# MCU098_01_MSPM0G3507_Target_Device.net
KiCad netlist of a schematic drawn in Altium Designer
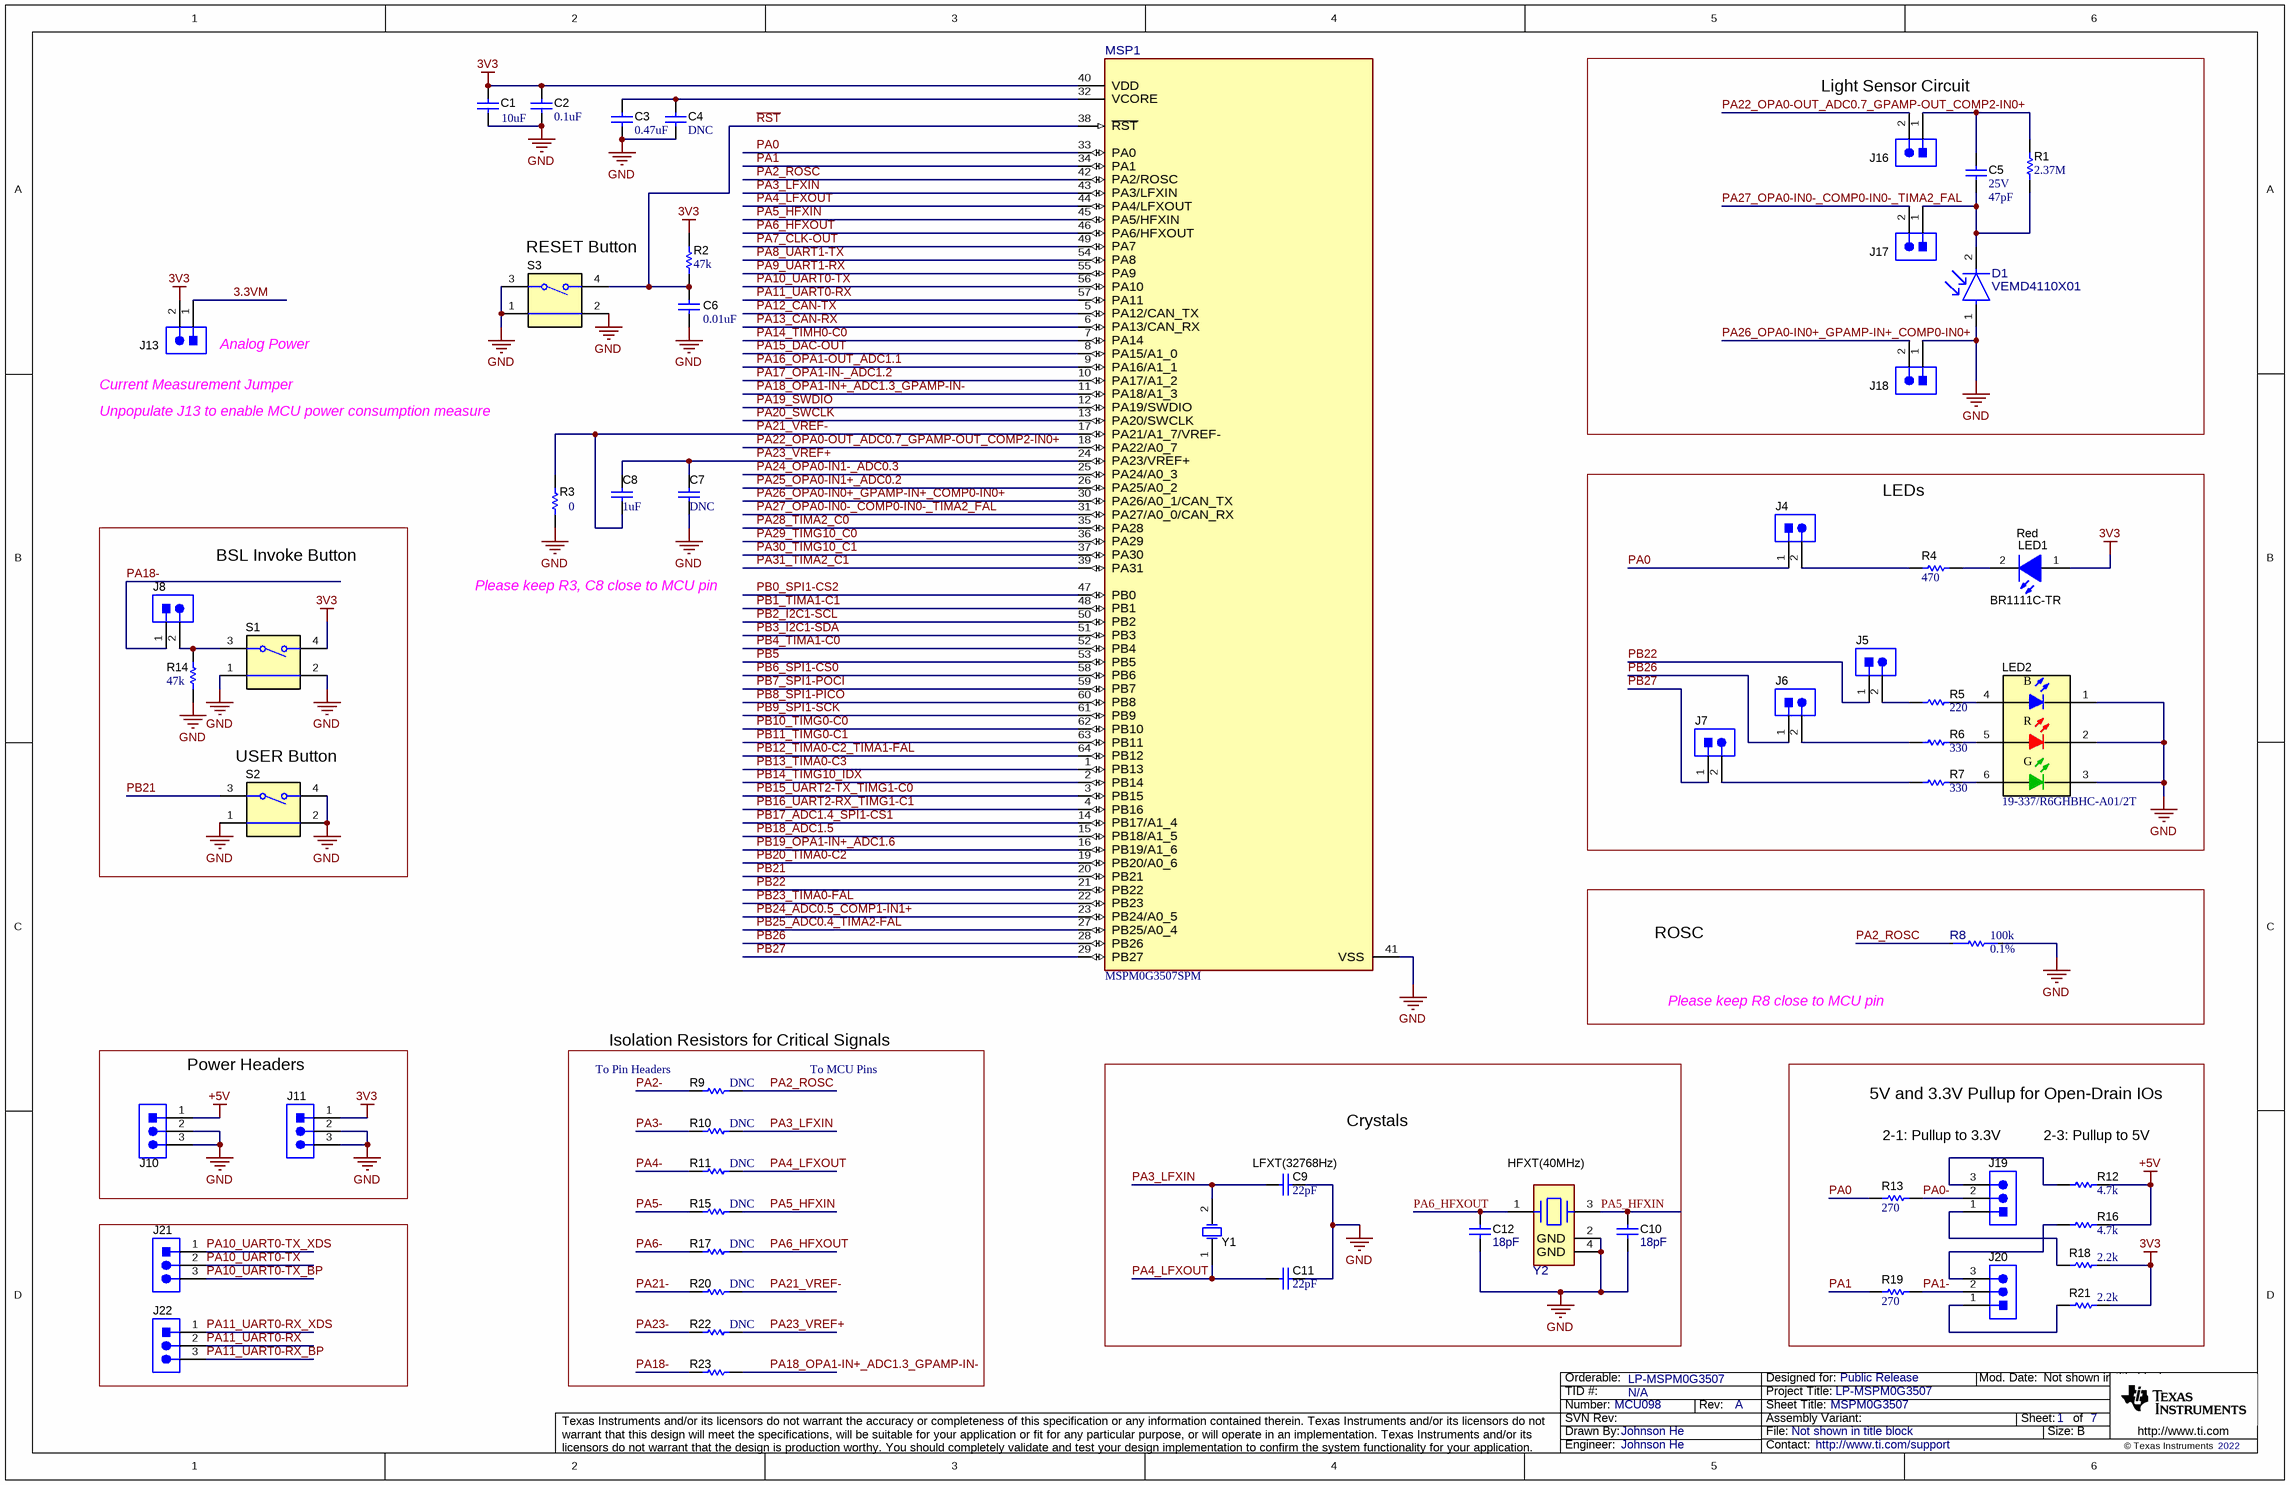
[diagram p0: MCU098_01_MSPM0G3507_Target_Device.SchDoc]

(export (version "E")
  (design (tool "Eeschema 10.0.6"))
  (components
    (comp (ref "C1")
      (value "GRM188R60J106ME84")
      (footprint "0603")
      (description "CAP, CERM, 10 uF, 6.3 V, +/- 20%, X5R, 0603")
      (fields
        (field (name "MANUFACTURER") "MuRata")
        (field (name "VALUEDISPLAYED") "10uF")
        (field (name "PUBLISHER") "Texas Instruments")
      )
      (libsource (lib "Altium Vault - TI") (part "Capacitor"))
    )
    (comp (ref "C2")
      (value "GRM155R61H104ME14D")
      (footprint "0402")
      (description "CAP, CERM, 0.1 uF, 50 V, +/- 20%, X5R, 0402")
      (fields
        (field (name "MANUFACTURER") "MuRata")
        (field (name "VALUEDISPLAYED") "0.1uF")
        (field (name "PUBLISHER") "Texas Instruments")
      )
      (libsource (lib "Altium Vault - TI") (part "Capacitor"))
    )
    (comp (ref "C3")
      (value "GRM155R60J474KE19D")
      (footprint "0402")
      (description "CAP, CERM, 0.47 uF, 6.3 V, +/- 10%, X5R, 0402")
      (fields
        (field (name "MANUFACTURER") "MuRata")
        (field (name "VALUEDISPLAYED") "0.47uF")
        (field (name "PUBLISHER") "Texas Instruments")
      )
      (libsource (lib "Altium Vault - TI") (part "Capacitor"))
    )
    (comp (ref "C4")
      (value "GRM155R61H104ME14D")
      (footprint "0402")
      (description "CAP, CERM, 0.1 uF, 50 V, +/- 20%, X5R, 0402")
      (fields
        (field (name "MANUFACTURER") "MuRata")
        (field (name "VALUEDISPLAYED") "DNC")
        (field (name "PUBLISHER") "Texas Instruments")
      )
      (libsource (lib "Altium Vault - TI") (part "Capacitor"))
    )
    (comp (ref "C5")
      (value "GRM1555C1E470JA01D")
      (footprint "0402")
      (description "CAP, CERM, 47 pF, 25 V, +/- 5%, C0G/NP0, 0402")
      (fields
        (field (name "MANUFACTURER") "MuRata")
        (field (name "VDC_V") "25V")
        (field (name "VALUEDISPLAYED") "47pF")
        (field (name "PUBLISHER") "Texas Instruments")
      )
      (libsource (lib "Altium Vault - TI") (part "Capacitor"))
    )
    (comp (ref "C6")
      (value "GRM155R61C103KA01D")
      (footprint "0402")
      (description "CAP, CERM, 0.01 uF, 16 V, +/- 10%, X5R, 0402")
      (fields
        (field (name "MANUFACTURER") "MuRata")
        (field (name "VALUEDISPLAYED") "0.01uF")
        (field (name "PUBLISHER") "Texas Instruments")
      )
      (libsource (lib "Altium Vault - TI") (part "Capacitor"))
    )
    (comp (ref "C7")
      (value "C1608X5R1E105K080AC")
      (footprint "0603")
      (description "CAP, CERM, 1 uF, 25 V, +/- 10%, X5R, 0603")
      (fields
        (field (name "MANUFACTURER") "TDK")
        (field (name "VALUEDISPLAYED") "DNC")
        (field (name "PUBLISHER") "Texas Instruments")
      )
      (libsource (lib "Altium Vault - TI") (part "Capacitor"))
    )
    (comp (ref "C8")
      (value "1uF")
      (footprint "0603")
      (description "CAP, CERM, 1 uF, 25 V, +/- 10%, X5R, 0603")
      (fields
        (field (name "MANUFACTURER") "TDK")
        (field (name "PARTNUMBER") "C1608X5R1E105K080AC")
        (field (name "PUBLISHER") "Texas Instruments")
      )
      (libsource (lib "Altium Vault - TI") (part "Capacitor"))
    )
    (comp (ref "C9")
      (value "GRM1555C1H220JA01D")
      (footprint "0402")
      (description "CAP, CERM, 22 pF, 50 V, +/- 5%, C0G/NP0, 0402")
      (fields
        (field (name "MANUFACTURER") "MuRata")
        (field (name "VALUEDISPLAYED") "22pF")
        (field (name "PUBLISHER") "Texas Instruments")
      )
      (libsource (lib "Altium Vault - TI") (part "Capacitor"))
    )
    (comp (ref "C10")
      (value "GRM1555C1H220JA01D")
      (footprint "0402")
      (description "CAP, CERM, 22 pF, 50 V, +/- 5%, C0G/NP0, 0402")
      (fields
        (field (name "MANUFACTURER") "MuRata")
        (field (name "VALUEDISPLAYED") "18pF")
        (field (name "PUBLISHER") "Texas Instruments")
      )
      (libsource (lib "Altium Vault - TI") (part "Capacitor"))
    )
    (comp (ref "C11")
      (value "GRM1555C1H220JA01D")
      (footprint "0402")
      (description "CAP, CERM, 22 pF, 50 V, +/- 5%, C0G/NP0, 0402")
      (fields
        (field (name "MANUFACTURER") "MuRata")
        (field (name "VALUEDISPLAYED") "22pF")
        (field (name "PUBLISHER") "Texas Instruments")
      )
      (libsource (lib "Altium Vault - TI") (part "Capacitor"))
    )
    (comp (ref "C12")
      (value "GRM1555C1H220JA01D")
      (footprint "0402")
      (description "CAP, CERM, 22 pF, 50 V, +/- 5%, C0G/NP0, 0402")
      (fields
        (field (name "MANUFACTURER") "MuRata")
        (field (name "VALUEDISPLAYED") "18pF")
        (field (name "PUBLISHER") "Texas Instruments")
      )
      (libsource (lib "Altium Vault - TI") (part "Capacitor"))
    )
    (comp (ref "D1")
      (value "VEMD4110X01")
      (footprint "FP-VEMD4110X01_0805-MFG")
      (description "Photodiode PIN Chip 910nm Automotive 2-Pin Case 0805(2012Metric) T/R")
      (fields
        (field (name "MANUFACTURER") "Vishay")
        (field (name "DIGIKEY PART NUMBER") "751-VEMD4110X01CT-ND")
      )
      (libsource (lib "Altium Vault - TI") (part "SYM-VEMD4110X01"))
    )
    (comp (ref "J4")
      (value "90120-0122")
      (footprint "CONN_90120-0122")
      (description "Header, 100mil, 2x1, Tin, TH")
      (fields (field (name "MANUFACTURER") "Molex") (field (name "PUBLISHER") "Texas Instruments"))
      (libsource (lib "Altium Vault - TI") (part "Header_2x1"))
    )
    (comp (ref "J5")
      (value "90120-0122")
      (footprint "CONN_90120-0122")
      (description "Header, 100mil, 2x1, Tin, TH")
      (fields (field (name "MANUFACTURER") "Molex") (field (name "PUBLISHER") "Texas Instruments"))
      (libsource (lib "Altium Vault - TI") (part "Header_2x1"))
    )
    (comp (ref "J6")
      (value "90120-0122")
      (footprint "CONN_90120-0122")
      (description "Header, 100mil, 2x1, Tin, TH")
      (fields (field (name "MANUFACTURER") "Molex") (field (name "PUBLISHER") "Texas Instruments"))
      (libsource (lib "Altium Vault - TI") (part "Header_2x1"))
    )
    (comp (ref "J7")
      (value "90120-0122")
      (footprint "CONN_90120-0122")
      (description "Header, 100mil, 2x1, Tin, TH")
      (fields (field (name "MANUFACTURER") "Molex") (field (name "PUBLISHER") "Texas Instruments"))
      (libsource (lib "Altium Vault - TI") (part "Header_2x1"))
    )
    (comp (ref "J8")
      (value "90120-0122")
      (footprint "CONN_90120-0122")
      (description "Header, 100mil, 2x1, Tin, TH")
      (fields (field (name "MANUFACTURER") "Molex") (field (name "PUBLISHER") "Texas Instruments"))
      (libsource (lib "Altium Vault - TI") (part "Header_2x1"))
    )
    (comp (ref "J10")
      (value "PEC03SAAN")
      (footprint "PEC03SAAN_Launchpad_5V0")
      (description "Header, 100mil, 3x1, Tin, TH")
      (fields
        (field (name "MANUFACTURER") "Sullins Connector Solutions")
        (field (name "PUBLISHER") "Texas Instruments")
      )
      (libsource (lib "Altium Vault - TI") (part "Header_3x1_Launchpad"))
    )
    (comp (ref "J11")
      (value "PEC03SAAN")
      (footprint "PEC03SAAN_Launchpad_3V3")
      (description "Header, 100mil, 3x1, Tin, TH")
      (fields
        (field (name "MANUFACTURER") "Sullins Connector Solutions")
        (field (name "PUBLISHER") "Texas Instruments")
      )
      (libsource (lib "Altium Vault - TI") (part "Header_3x1_Launchpad"))
    )
    (comp (ref "J13")
      (value "90120-0122")
      (footprint "CONN_90120-0122")
      (description "Header, 100mil, 2x1, Tin, TH")
      (fields (field (name "MANUFACTURER") "Molex") (field (name "PUBLISHER") "Texas Instruments"))
      (libsource (lib "") (part "Header_2x1_1"))
    )
    (comp (ref "J16")
      (value "90120-0122")
      (footprint "CONN_90120-0122")
      (description "Header, 100mil, 2x1, Tin, TH")
      (fields (field (name "MANUFACTURER") "Molex") (field (name "PUBLISHER") "Texas Instruments"))
      (libsource (lib "") (part "Header_2x1_1"))
    )
    (comp (ref "J17")
      (value "90120-0122")
      (footprint "CONN_90120-0122")
      (description "Header, 100mil, 2x1, Tin, TH")
      (fields (field (name "MANUFACTURER") "Molex") (field (name "PUBLISHER") "Texas Instruments"))
      (libsource (lib "") (part "Header_2x1_1"))
    )
    (comp (ref "J18")
      (value "90120-0122")
      (footprint "CONN_90120-0122")
      (description "Header, 100mil, 2x1, Tin, TH")
      (fields (field (name "MANUFACTURER") "Molex") (field (name "PUBLISHER") "Texas Instruments"))
      (libsource (lib "") (part "Header_2x1_1"))
    )
    (comp (ref "J19")
      (value "PEC03SAAN")
      (footprint "CONN_PEC03SAAN")
      (description "Header, 100mil, 3x1, Tin, TH")
      (fields
        (field (name "MANUFACTURER") "Sullins Connector Solutions")
        (field (name "PUBLISHER") "Texas Instruments")
      )
      (libsource (lib "") (part "Header_3x1_Launchpad_1"))
    )
    (comp (ref "J20")
      (value "PEC03SAAN")
      (footprint "CONN_PEC03SAAN")
      (description "Header, 100mil, 3x1, Tin, TH")
      (fields
        (field (name "MANUFACTURER") "Sullins Connector Solutions")
        (field (name "PUBLISHER") "Texas Instruments")
      )
      (libsource (lib "") (part "Header_3x1_Launchpad_1"))
    )
    (comp (ref "J21")
      (value "PEC03SAAN")
      (footprint "CONN_PEC03SAAN")
      (description "Header, 100mil, 3x1, Tin, TH")
      (fields
        (field (name "MANUFACTURER") "Sullins Connector Solutions")
        (field (name "PUBLISHER") "Texas Instruments")
      )
      (libsource (lib "Altium Vault - TI") (part "Header_3x1_Launchpad"))
    )
    (comp (ref "J22")
      (value "PEC03SAAN")
      (footprint "CONN_PEC03SAAN")
      (description "Header, 100mil, 3x1, Tin, TH")
      (fields
        (field (name "MANUFACTURER") "Sullins Connector Solutions")
        (field (name "PUBLISHER") "Texas Instruments")
      )
      (libsource (lib "Altium Vault - TI") (part "Header_3x1_Launchpad"))
    )
    (comp (ref "LED1")
      (value "BR1111C-TR")
      (footprint "1111C_Red")
      (description "LED, Red, SMD")
      (fields (field (name "ALTIUM_VALUE") "Red") (field (name "MANUFACTURER") "Stanley Electric Co., LTD"))
      (libsource (lib "Altium Vault - TI") (part "LED"))
    )
    (comp (ref "LED2")
      (value "19-337/R6GHBHC-A01/2T")
      (footprint "19-337_RGB")
      (description "LED, RGB, SMD")
      (fields (field (name "MANUFACTURER") "Everlight") (field (name "PUBLISHER") "Texas Instruments"))
      (libsource (lib "Altium Vault - TI") (part "LED_RGB_A456K123"))
    )
    (comp (ref "MSP1")
      (value "MSPM0G3507SPM")
      (footprint "PM0064A-MFG")
      (description "Mixed-Signal Microcontrollers With CAN-FD Interface LQFP64")
      (fields (field (name "PARTNUMBER") "MSPM0G3507SPM") (field (name "MANUFACTURER") "Texas Instruments"))
      (libsource (lib "Altium Vault - TI") (part "SYM-MSPM0G3507SPM"))
    )
    (comp (ref "R1")
      (value "CRCW06032M37FKEA")
      (footprint "0603")
      (description "RES, 2.37 M, 1%, 0.1 W, 0603")
      (fields
        (field (name "MANUFACTURER") "Vishay-Dale")
        (field (name "VALUEDISPLAYED") "2.37M")
        (field (name "PUBLISHER") "Texas Instruments")
      )
      (libsource (lib "Altium Vault - TI") (part "Resistor"))
    )
    (comp (ref "R2")
      (value "CRCW040247K0JNED")
      (footprint "0402")
      (description "RES, 47 k, 5%, 0.063 W, 0402")
      (fields
        (field (name "MANUFACTURER") "Vishay-Dale")
        (field (name "VALUEDISPLAYED") "47k")
        (field (name "PUBLISHER") "Texas Instruments")
      )
      (libsource (lib "Altium Vault - TI") (part "Resistor"))
    )
    (comp (ref "R3")
      (value "0")
      (footprint "0603")
      (description "RES, 0, 5%, 0.1 W, 0603")
      (fields (field (name "MANUFACTURER") "Yageo") (field (name "PARTNUMBER") "RC0603JR-070RL"))
      (libsource (lib "Altium Vault - TI") (part "Resistor"))
    )
    (comp (ref "R4")
      (value "CRCW0402470RJNED")
      (footprint "0402")
      (description "RES, 470, 5%, 0.063 W, 0402")
      (fields
        (field (name "MANUFACTURER") "Vishay-Dale")
        (field (name "VALUEDISPLAYED") "470")
        (field (name "PUBLISHER") "Texas Instruments")
      )
      (libsource (lib "Altium Vault - TI") (part "Resistor"))
    )
    (comp (ref "R5")
      (value "CRCW0402220RJNED")
      (footprint "0402")
      (description "RES, 220, 5%, 0.063 W, 0402")
      (fields
        (field (name "MANUFACTURER") "Vishay-Dale")
        (field (name "VALUEDISPLAYED") "220")
        (field (name "PUBLISHER") "Texas Instruments")
      )
      (libsource (lib "Altium Vault - TI") (part "Resistor"))
    )
    (comp (ref "R6")
      (value "CRCW0402330RJNED")
      (footprint "0402")
      (description "RES, 330, 5%, 0.063 W, 0402")
      (fields
        (field (name "MANUFACTURER") "Vishay-Dale")
        (field (name "VALUEDISPLAYED") "330")
        (field (name "PUBLISHER") "Texas Instruments")
      )
      (libsource (lib "Altium Vault - TI") (part "Resistor"))
    )
    (comp (ref "R7")
      (value "CRCW0402330RJNED")
      (footprint "0402")
      (description "RES, 330, 5%, 0.063 W, 0402")
      (fields
        (field (name "MANUFACTURER") "Vishay-Dale")
        (field (name "VALUEDISPLAYED") "330")
        (field (name "PUBLISHER") "Texas Instruments")
      )
      (libsource (lib "Altium Vault - TI") (part "Resistor"))
    )
    (comp (ref "R8")
      (value "ERA-2AEB104X")
      (footprint "FP-ERA-2AEB104X_0402-MFG")
      (description "Res Thin Film 0402 100K Ohm 0.1% 1/16W ±25ppm/°C Molded SMD SMD Punched Carrier T/R")
      (fields
        (field (name "DIGIKEY PART NUMBER") "P100KDCCT-ND")
        (field (name "MANUFACTURER") "Panasonic")
        (field (name "TOLERANCE_%") "0.1%")
        (field (name "RES_OHM") "100k")
      )
      (libsource (lib "Altium Vault - TI") (part "SYM-ERA-2AEB104X"))
    )
    (comp (ref "R9")
      (value "RC0402JR-070RL")
      (footprint "0402")
      (description "RES, 0, 5%, 0.063 W, 0402")
      (fields
        (field (name "MANUFACTURER") "Yageo America")
        (field (name "VALUEDISPLAYED") "DNC")
        (field (name "PUBLISHER") "Texas Instruments")
      )
      (libsource (lib "Altium Vault - TI") (part "Resistor"))
    )
    (comp (ref "R10")
      (value "RC0402JR-070RL")
      (footprint "0402")
      (description "RES, 0, 5%, 0.063 W, 0402")
      (fields
        (field (name "MANUFACTURER") "Yageo America")
        (field (name "VALUEDISPLAYED") "DNC")
        (field (name "PUBLISHER") "Texas Instruments")
      )
      (libsource (lib "Altium Vault - TI") (part "Resistor"))
    )
    (comp (ref "R11")
      (value "RC0402JR-070RL")
      (footprint "0402")
      (description "RES, 0, 5%, 0.063 W, 0402")
      (fields
        (field (name "MANUFACTURER") "Yageo America")
        (field (name "VALUEDISPLAYED") "DNC")
        (field (name "PUBLISHER") "Texas Instruments")
      )
      (libsource (lib "Altium Vault - TI") (part "Resistor"))
    )
    (comp (ref "R12")
      (value "RC0603JR-074K7L")
      (footprint "0603")
      (description "RES, 4.7 k, 5%, 0.1 W, 0603")
      (fields (field (name "MANUFACTURER") "Yageo") (field (name "VALUEDISPLAYED") "4.7k"))
      (libsource (lib "Altium Vault - TI") (part "Resistor"))
    )
    (comp (ref "R13")
      (value "CRCW0402270RJNED")
      (footprint "0402")
      (description "RES, 270, 5%, 0.063 W, 0402")
      (fields
        (field (name "MANUFACTURER") "Vishay-Dale")
        (field (name "VALUEDISPLAYED") "270")
        (field (name "PUBLISHER") "Texas Instruments")
      )
      (libsource (lib "Altium Vault - TI") (part "Resistor"))
    )
    (comp (ref "R14")
      (value "CRCW040247K0JNED")
      (footprint "0402")
      (description "RES, 47 k, 5%, 0.063 W, 0402")
      (fields
        (field (name "MANUFACTURER") "Vishay-Dale")
        (field (name "VALUEDISPLAYED") "47k")
        (field (name "PUBLISHER") "Texas Instruments")
      )
      (libsource (lib "Altium Vault - TI") (part "Resistor"))
    )
    (comp (ref "R15")
      (value "RC0402JR-070RL")
      (footprint "0402")
      (description "RES, 0, 5%, 0.063 W, 0402")
      (fields
        (field (name "MANUFACTURER") "Yageo America")
        (field (name "VALUEDISPLAYED") "DNC")
        (field (name "PUBLISHER") "Texas Instruments")
      )
      (libsource (lib "Altium Vault - TI") (part "Resistor"))
    )
    (comp (ref "R16")
      (value "RC0603JR-074K7L")
      (footprint "0603")
      (description "RES, 4.7 k, 5%, 0.1 W, 0603")
      (fields (field (name "MANUFACTURER") "Yageo") (field (name "VALUEDISPLAYED") "4.7k"))
      (libsource (lib "Altium Vault - TI") (part "Resistor"))
    )
    (comp (ref "R17")
      (value "RC0402JR-070RL")
      (footprint "0402")
      (description "RES, 0, 5%, 0.063 W, 0402")
      (fields
        (field (name "MANUFACTURER") "Yageo America")
        (field (name "VALUEDISPLAYED") "DNC")
        (field (name "PUBLISHER") "Texas Instruments")
      )
      (libsource (lib "Altium Vault - TI") (part "Resistor"))
    )
    (comp (ref "R18")
      (value "RC0603JR-0710KL")
      (footprint "0603")
      (description "RES, 2.2 k, 5%, 0.1 W, 0603")
      (fields
        (field (name "PARTNUMBER") "RC0603JR-072K2L")
        (field (name "MANUFACTURER") "Yageo")
        (field (name "VALUEDISPLAYED") "2.2k")
      )
      (libsource (lib "Altium Vault - TI") (part "Resistor"))
    )
    (comp (ref "R19")
      (value "CRCW0402270RJNED")
      (footprint "0402")
      (description "RES, 270, 5%, 0.063 W, 0402")
      (fields
        (field (name "MANUFACTURER") "Vishay-Dale")
        (field (name "VALUEDISPLAYED") "270")
        (field (name "PUBLISHER") "Texas Instruments")
      )
      (libsource (lib "Altium Vault - TI") (part "Resistor"))
    )
    (comp (ref "R20")
      (value "RC0402JR-070RL")
      (footprint "0402")
      (description "RES, 0, 5%, 0.063 W, 0402")
      (fields
        (field (name "MANUFACTURER") "Yageo America")
        (field (name "VALUEDISPLAYED") "DNC")
        (field (name "PUBLISHER") "Texas Instruments")
      )
      (libsource (lib "Altium Vault - TI") (part "Resistor"))
    )
    (comp (ref "R21")
      (value "RC0603JR-0710KL")
      (footprint "0603")
      (description "RES, 2.2 k, 5%, 0.1 W, 0603")
      (fields
        (field (name "PARTNUMBER") "RC0603JR-072K2L")
        (field (name "MANUFACTURER") "Yageo")
        (field (name "VALUEDISPLAYED") "2.2k")
      )
      (libsource (lib "Altium Vault - TI") (part "Resistor"))
    )
    (comp (ref "R22")
      (value "RC0402JR-070RL")
      (footprint "0402")
      (description "RES, 0, 5%, 0.063 W, 0402")
      (fields
        (field (name "MANUFACTURER") "Yageo America")
        (field (name "VALUEDISPLAYED") "DNC")
        (field (name "PUBLISHER") "Texas Instruments")
      )
      (libsource (lib "Altium Vault - TI") (part "Resistor"))
    )
    (comp (ref "R23")
      (value "RC0402JR-070RL")
      (footprint "0402")
      (description "RES, 0, 5%, 0.063 W, 0402")
      (fields (field (name "MANUFACTURER") "Yageo America") (field (name "PUBLISHER") "Texas Instruments"))
      (libsource (lib "Altium Vault - TI") (part "Resistor"))
    )
    (comp (ref "S1")
      (value "1188E-1K2-V-TR")
      (footprint "SW_1188E")
      (description "Switch, SPST, 0.05 A, 12 VDC, SMD")
      (fields (field (name "MANUFACTURER") "Diptronics") (field (name "PUBLISHER") "Texas Instruments"))
      (libsource (lib "Altium Vault - TI") (part "SW_1188E"))
    )
    (comp (ref "S2")
      (value "1188E-1K2-V-TR")
      (footprint "SW_1188E")
      (description "Switch, SPST, 0.05 A, 12 VDC, SMD")
      (fields (field (name "MANUFACTURER") "Diptronics") (field (name "PUBLISHER") "Texas Instruments"))
      (libsource (lib "Altium Vault - TI") (part "SW_1188E"))
    )
    (comp (ref "S3")
      (value "1188E-1K2-V-TR")
      (footprint "SW_1188E")
      (description "Switch, SPST, 0.05 A, 12 VDC, SMD")
      (fields (field (name "MANUFACTURER") "Diptronics") (field (name "PUBLISHER") "Texas Instruments"))
      (libsource (lib "Altium Vault - TI") (part "SW_1188E"))
    )
    (comp (ref "Y1")
      (value "X1A0001410014")
      (footprint "Epson_FC-135")
      (description "Crystal, 32.768 KHz, 12.5 pF, SMD")
      (fields (field (name "MANUFACTURER") "Epson") (field (name "PUBLISHER") "Texas Instruments"))
      (libsource (lib "Altium Vault - TI") (part "Xtal"))
    )
    (comp (ref "Y2")
      (value "X1E0000210179")
      (footprint "FP-X1E0000210179_TSX-3225-MFG")
      (description "Crystal 40MHz ±10ppm (Tol) ±20ppm (Stability) 12pF FUND 40Ohm 4-Pin Mini-CSMD T/R")
      (fields (field (name "MANUFACTURER") "Seiko Epson"))
      (libsource (lib "Altium Vault - TI") (part "SYM-X1E0000210179"))
    )
  )
  (nets
    (net (code "1") (name "+5V") (class "Default")
      (node (ref "J10") (pin "1") (pinfunction "1_1") (pintype "passive"))
      (node (ref "R12") (pin "2") (pinfunction "2_2") (pintype "passive"))
      (node (ref "R16") (pin "2") (pinfunction "2_2") (pintype "passive"))
    )
    (net (code "2") (name "/3.3VM") (class "Default")
      (node (ref "J13") (pin "1") (pinfunction "1_1") (pintype "passive"))
    )
    (net (code "3") (name "/PA0") (class "Default")
      (node (ref "J4") (pin "1") (pinfunction "1_1") (pintype "passive"))
      (node (ref "MSP1") (pin "33") (pinfunction "PA0_33") (pintype "bidirectional"))
      (node (ref "R13") (pin "1") (pinfunction "1_1") (pintype "passive"))
    )
    (net (code "4") (name "/PA0-") (class "Default")
      (node (ref "J19") (pin "2") (pinfunction "2_2") (pintype "passive"))
      (node (ref "R13") (pin "2") (pinfunction "2_2") (pintype "passive"))
    )
    (net (code "5") (name "/PA1") (class "Default")
      (node (ref "MSP1") (pin "34") (pinfunction "PA1_34") (pintype "bidirectional"))
      (node (ref "R19") (pin "1") (pinfunction "1_1") (pintype "passive"))
    )
    (net (code "6") (name "/PA1-") (class "Default")
      (node (ref "J20") (pin "2") (pinfunction "2_2") (pintype "passive"))
      (node (ref "R19") (pin "2") (pinfunction "2_2") (pintype "passive"))
    )
    (net (code "7") (name "/PA2-") (class "Default")
      (node (ref "R9") (pin "1") (pinfunction "1_1") (pintype "passive"))
    )
    (net (code "8") (name "/PA2_ROSC") (class "Default")
      (node (ref "MSP1") (pin "42") (pinfunction "PA2/ROSC_42") (pintype "bidirectional"))
      (node (ref "R8") (pin "1") (pinfunction "1_1") (pintype "passive"))
      (node (ref "R9") (pin "2") (pinfunction "2_2") (pintype "passive"))
    )
    (net (code "9") (name "/PA3-") (class "Default")
      (node (ref "R10") (pin "1") (pinfunction "1_1") (pintype "passive"))
    )
    (net (code "10") (name "/PA3_LFXIN") (class "Default")
      (node (ref "C9") (pin "2") (pinfunction "2_2") (pintype "passive"))
      (node (ref "MSP1") (pin "43") (pinfunction "PA3/LFXIN_43") (pintype "bidirectional"))
      (node (ref "R10") (pin "2") (pinfunction "2_2") (pintype "passive"))
      (node (ref "Y1") (pin "2") (pinfunction "OSC2_2") (pintype "passive"))
    )
    (net (code "11") (name "/PA4-") (class "Default")
      (node (ref "R11") (pin "1") (pinfunction "1_1") (pintype "passive"))
    )
    (net (code "12") (name "/PA4_LFXOUT") (class "Default")
      (node (ref "C11") (pin "2") (pinfunction "2_2") (pintype "passive"))
      (node (ref "MSP1") (pin "44") (pinfunction "PA4/LFXOUT_44") (pintype "bidirectional"))
      (node (ref "R11") (pin "2") (pinfunction "2_2") (pintype "passive"))
      (node (ref "Y1") (pin "1") (pinfunction "OSC1_1") (pintype "passive"))
    )
    (net (code "13") (name "/PA5-") (class "Default")
      (node (ref "R15") (pin "1") (pinfunction "1_1") (pintype "passive"))
    )
    (net (code "14") (name "/PA5_HFXIN") (class "Default")
      (node (ref "C10") (pin "2") (pinfunction "2_2") (pintype "passive"))
      (node (ref "MSP1") (pin "45") (pinfunction "PA5/HFXIN_45") (pintype "bidirectional"))
      (node (ref "R15") (pin "2") (pinfunction "2_2") (pintype "passive"))
      (node (ref "Y2") (pin "3") (pinfunction "3_3") (pintype "passive"))
    )
    (net (code "15") (name "/PA6-") (class "Default")
      (node (ref "R17") (pin "1") (pinfunction "1_1") (pintype "passive"))
    )
    (net (code "16") (name "/PA6_HFXOUT") (class "Default")
      (node (ref "C12") (pin "2") (pinfunction "2_2") (pintype "passive"))
      (node (ref "MSP1") (pin "46") (pinfunction "PA6/HFXOUT_46") (pintype "bidirectional"))
      (node (ref "R17") (pin "2") (pinfunction "2_2") (pintype "passive"))
      (node (ref "Y2") (pin "1") (pinfunction "1_1") (pintype "passive"))
    )
    (net (code "17") (name "/PA7_CLK-OUT") (class "Default")
      (node (ref "MSP1") (pin "49") (pinfunction "PA7_49") (pintype "bidirectional"))
    )
    (net (code "18") (name "/PA8_UART1-TX") (class "Default")
      (node (ref "MSP1") (pin "54") (pinfunction "PA8_54") (pintype "bidirectional"))
    )
    (net (code "19") (name "/PA9_UART1-RX") (class "Default")
      (node (ref "MSP1") (pin "55") (pinfunction "PA9_55") (pintype "bidirectional"))
    )
    (net (code "20") (name "/PA10_UART0-TX") (class "Default")
      (node (ref "J21") (pin "2") (pinfunction "2_2") (pintype "passive"))
      (node (ref "MSP1") (pin "56") (pinfunction "PA10_56") (pintype "bidirectional"))
    )
    (net (code "21") (name "/PA10_UART0-TX_BP") (class "Default")
      (node (ref "J21") (pin "3") (pinfunction "3_3") (pintype "passive"))
    )
    (net (code "22") (name "/PA10_UART0-TX_XDS") (class "Default")
      (node (ref "J21") (pin "1") (pinfunction "1_1") (pintype "passive"))
    )
    (net (code "23") (name "/PA11_UART0-RX") (class "Default")
      (node (ref "J22") (pin "2") (pinfunction "2_2") (pintype "passive"))
      (node (ref "MSP1") (pin "57") (pinfunction "PA11_57") (pintype "bidirectional"))
    )
    (net (code "24") (name "/PA11_UART0-RX_BP") (class "Default")
      (node (ref "J22") (pin "3") (pinfunction "3_3") (pintype "passive"))
    )
    (net (code "25") (name "/PA11_UART0-RX_XDS") (class "Default")
      (node (ref "J22") (pin "1") (pinfunction "1_1") (pintype "passive"))
    )
    (net (code "26") (name "/PA12_CAN-TX") (class "Default")
      (node (ref "MSP1") (pin "5") (pinfunction "PA12/CAN_TX_5") (pintype "bidirectional"))
    )
    (net (code "27") (name "/PA13_CAN-RX") (class "Default")
      (node (ref "MSP1") (pin "6") (pinfunction "PA13/CAN_RX_6") (pintype "bidirectional"))
    )
    (net (code "28") (name "/PA14_TIMH0-C0") (class "Default")
      (node (ref "MSP1") (pin "7") (pinfunction "PA14_7") (pintype "bidirectional"))
    )
    (net (code "29") (name "/PA15_DAC-OUT") (class "Default")
      (node (ref "MSP1") (pin "8") (pinfunction "PA15/A1_0_8") (pintype "bidirectional"))
    )
    (net (code "30") (name "/PA16_OPA1-OUT_ADC1.1") (class "Default")
      (node (ref "MSP1") (pin "9") (pinfunction "PA16/A1_1_9") (pintype "bidirectional"))
    )
    (net (code "31") (name "/PA17_OPA1-IN-_ADC1.2") (class "Default")
      (node (ref "MSP1") (pin "10") (pinfunction "PA17/A1_2_10") (pintype "bidirectional"))
    )
    (net (code "32") (name "/PA18-") (class "Default")
      (node (ref "J8") (pin "1") (pinfunction "1_1") (pintype "passive"))
      (node (ref "R23") (pin "1") (pinfunction "1_1") (pintype "passive"))
    )
    (net (code "33") (name "/PA18_OPA1-IN+_ADC1.3_GPAMP-IN-") (class "Default")
      (node (ref "MSP1") (pin "11") (pinfunction "PA18/A1_3_11") (pintype "bidirectional"))
      (node (ref "R23") (pin "2") (pinfunction "2_2") (pintype "passive"))
    )
    (net (code "34") (name "/PA19_SWDIO") (class "Default")
      (node (ref "MSP1") (pin "12") (pinfunction "PA19/SWDIO_12") (pintype "bidirectional"))
    )
    (net (code "35") (name "/PA20_SWCLK") (class "Default")
      (node (ref "MSP1") (pin "13") (pinfunction "PA20/SWCLK_13") (pintype "bidirectional"))
    )
    (net (code "36") (name "/PA21-") (class "Default")
      (node (ref "R20") (pin "1") (pinfunction "1_1") (pintype "passive"))
    )
    (net (code "37") (name "/PA21_VREF-") (class "Default")
      (node (ref "C8") (pin "2") (pinfunction "2_2") (pintype "passive"))
      (node (ref "MSP1") (pin "17") (pinfunction "PA21/A1_7/VREF-_17") (pintype "bidirectional"))
      (node (ref "R20") (pin "2") (pinfunction "2_2") (pintype "passive"))
      (node (ref "R3") (pin "2") (pinfunction "2_2") (pintype "passive"))
    )
    (net (code "38") (name "/PA22_OPA0-OUT_ADC0.7_GPAMP-OUT_COMP2-IN0+") (class "Default")
      (node (ref "J16") (pin "2") (pinfunction "2_2") (pintype "passive"))
      (node (ref "MSP1") (pin "18") (pinfunction "PA22/A0_7_18") (pintype "bidirectional"))
    )
    (net (code "39") (name "/PA23-") (class "Default")
      (node (ref "R22") (pin "1") (pinfunction "1_1") (pintype "passive"))
    )
    (net (code "40") (name "/PA23_VREF+") (class "Default")
      (node (ref "C7") (pin "1") (pinfunction "1_1") (pintype "passive"))
      (node (ref "C8") (pin "1") (pinfunction "1_1") (pintype "passive"))
      (node (ref "MSP1") (pin "24") (pinfunction "PA23/VREF+_24") (pintype "bidirectional"))
      (node (ref "R22") (pin "2") (pinfunction "2_2") (pintype "passive"))
    )
    (net (code "41") (name "/PA24_OPA0-IN1-_ADC0.3") (class "Default")
      (node (ref "MSP1") (pin "25") (pinfunction "PA24/A0_3_25") (pintype "bidirectional"))
    )
    (net (code "42") (name "/PA25_OPA0-IN1+_ADC0.2") (class "Default")
      (node (ref "MSP1") (pin "26") (pinfunction "PA25/A0_2_26") (pintype "bidirectional"))
    )
    (net (code "43") (name "/PA26_OPA0-IN0+_GPAMP-IN+_COMP0-IN0+") (class "Default")
      (node (ref "J18") (pin "2") (pinfunction "2_2") (pintype "passive"))
      (node (ref "MSP1") (pin "30") (pinfunction "PA26/A0_1/CAN_TX_30") (pintype "bidirectional"))
    )
    (net (code "44") (name "/PA27_OPA0-IN0-_COMP0-IN0-_TIMA2_FAL") (class "Default")
      (node (ref "J17") (pin "2") (pinfunction "2_2") (pintype "passive"))
      (node (ref "MSP1") (pin "31") (pinfunction "PA27/A0_0/CAN_RX_31") (pintype "bidirectional"))
    )
    (net (code "45") (name "/PA28_TIMA2_C0") (class "Default")
      (node (ref "MSP1") (pin "35") (pinfunction "PA28_35") (pintype "bidirectional"))
    )
    (net (code "46") (name "/PA29_TIMG10_C0") (class "Default")
      (node (ref "MSP1") (pin "36") (pinfunction "PA29_36") (pintype "bidirectional"))
    )
    (net (code "47") (name "/PA30_TIMG10_C1") (class "Default")
      (node (ref "MSP1") (pin "37") (pinfunction "PA30_37") (pintype "bidirectional"))
    )
    (net (code "48") (name "/PA31_TIMA2_C1") (class "Default")
      (node (ref "MSP1") (pin "39") (pinfunction "PA31_39") (pintype "bidirectional"))
    )
    (net (code "49") (name "/PB0_SPI1-CS2") (class "Default")
      (node (ref "MSP1") (pin "47") (pinfunction "PB0_47") (pintype "bidirectional"))
    )
    (net (code "50") (name "/PB1_TIMA1-C1") (class "Default")
      (node (ref "MSP1") (pin "48") (pinfunction "PB1_48") (pintype "bidirectional"))
    )
    (net (code "51") (name "/PB2_I2C1-SCL") (class "Default")
      (node (ref "MSP1") (pin "50") (pinfunction "PB2_50") (pintype "bidirectional"))
    )
    (net (code "52") (name "/PB3_I2C1-SDA") (class "Default")
      (node (ref "MSP1") (pin "51") (pinfunction "PB3_51") (pintype "bidirectional"))
    )
    (net (code "53") (name "/PB4_TIMA1-C0") (class "Default")
      (node (ref "MSP1") (pin "52") (pinfunction "PB4_52") (pintype "bidirectional"))
    )
    (net (code "54") (name "/PB5") (class "Default")
      (node (ref "MSP1") (pin "53") (pinfunction "PB5_53") (pintype "bidirectional"))
    )
    (net (code "55") (name "/PB6_SPI1-CS0") (class "Default")
      (node (ref "MSP1") (pin "58") (pinfunction "PB6_58") (pintype "bidirectional"))
    )
    (net (code "56") (name "/PB7_SPI1-POCI") (class "Default")
      (node (ref "MSP1") (pin "59") (pinfunction "PB7_59") (pintype "bidirectional"))
    )
    (net (code "57") (name "/PB8_SPI1-PICO") (class "Default")
      (node (ref "MSP1") (pin "60") (pinfunction "PB8_60") (pintype "bidirectional"))
    )
    (net (code "58") (name "/PB9_SPI1-SCK") (class "Default")
      (node (ref "MSP1") (pin "61") (pinfunction "PB9_61") (pintype "bidirectional"))
    )
    (net (code "59") (name "/PB10_TIMG0-C0") (class "Default")
      (node (ref "MSP1") (pin "62") (pinfunction "PB10_62") (pintype "bidirectional"))
    )
    (net (code "60") (name "/PB11_TIMG0-C1") (class "Default")
      (node (ref "MSP1") (pin "63") (pinfunction "PB11_63") (pintype "bidirectional"))
    )
    (net (code "61") (name "/PB12_TIMA0-C2_TIMA1-FAL") (class "Default")
      (node (ref "MSP1") (pin "64") (pinfunction "PB12_64") (pintype "bidirectional"))
    )
    (net (code "62") (name "/PB13_TIMA0-C3") (class "Default")
      (node (ref "MSP1") (pin "1") (pinfunction "PB13_1") (pintype "bidirectional"))
    )
    (net (code "63") (name "/PB14_TIMG10_IDX") (class "Default")
      (node (ref "MSP1") (pin "2") (pinfunction "PB14_2") (pintype "bidirectional"))
    )
    (net (code "64") (name "/PB15_UART2-TX_TIMG1-C0") (class "Default")
      (node (ref "MSP1") (pin "3") (pinfunction "PB15_3") (pintype "bidirectional"))
    )
    (net (code "65") (name "/PB16_UART2-RX_TIMG1-C1") (class "Default")
      (node (ref "MSP1") (pin "4") (pinfunction "PB16_4") (pintype "bidirectional"))
    )
    (net (code "66") (name "/PB17_ADC1.4_SPI1-CS1") (class "Default")
      (node (ref "MSP1") (pin "14") (pinfunction "PB17/A1_4_14") (pintype "bidirectional"))
    )
    (net (code "67") (name "/PB18_ADC1.5") (class "Default")
      (node (ref "MSP1") (pin "15") (pinfunction "PB18/A1_5_15") (pintype "bidirectional"))
    )
    (net (code "68") (name "/PB19_OPA1-IN+_ADC1.6") (class "Default")
      (node (ref "MSP1") (pin "16") (pinfunction "PB19/A1_6_16") (pintype "bidirectional"))
    )
    (net (code "69") (name "/PB20_TIMA0-C2") (class "Default")
      (node (ref "MSP1") (pin "19") (pinfunction "PB20/A0_6_19") (pintype "bidirectional"))
    )
    (net (code "70") (name "/PB21") (class "Default")
      (node (ref "MSP1") (pin "20") (pinfunction "PB21_20") (pintype "bidirectional"))
      (node (ref "S2") (pin "3") (pinfunction "3_3") (pintype "passive"))
    )
    (net (code "71") (name "/PB22") (class "Default")
      (node (ref "J5") (pin "1") (pinfunction "1_1") (pintype "passive"))
      (node (ref "MSP1") (pin "21") (pinfunction "PB22_21") (pintype "bidirectional"))
    )
    (net (code "72") (name "/PB23_TIMA0-FAL") (class "Default")
      (node (ref "MSP1") (pin "22") (pinfunction "PB23_22") (pintype "bidirectional"))
    )
    (net (code "73") (name "/PB24_ADC0.5_COMP1-IN1+") (class "Default")
      (node (ref "MSP1") (pin "23") (pinfunction "PB24/A0_5_23") (pintype "bidirectional"))
    )
    (net (code "74") (name "/PB25_ADC0.4_TIMA2-FAL") (class "Default")
      (node (ref "MSP1") (pin "27") (pinfunction "PB25/A0_4_27") (pintype "bidirectional"))
    )
    (net (code "75") (name "/PB26") (class "Default")
      (node (ref "J6") (pin "1") (pinfunction "1_1") (pintype "passive"))
      (node (ref "MSP1") (pin "28") (pinfunction "PB26_28") (pintype "bidirectional"))
    )
    (net (code "76") (name "/PB27") (class "Default")
      (node (ref "J7") (pin "1") (pinfunction "1_1") (pintype "passive"))
      (node (ref "MSP1") (pin "29") (pinfunction "PB27_29") (pintype "bidirectional"))
    )
    (net (code "77") (name "/~{RST}") (class "Default")
      (node (ref "C6") (pin "1") (pinfunction "1_1") (pintype "passive"))
      (node (ref "MSP1") (pin "38") (pinfunction "~{RST}_38") (pintype "input"))
      (node (ref "R2") (pin "1") (pinfunction "1_1") (pintype "passive"))
      (node (ref "S3") (pin "4") (pinfunction "4_4") (pintype "passive"))
    )
    (net (code "78") (name "3V3") (class "Default")
      (node (ref "C1") (pin "1") (pinfunction "1_1") (pintype "passive"))
      (node (ref "C2") (pin "1") (pinfunction "1_1") (pintype "passive"))
      (node (ref "J11") (pin "1") (pinfunction "1_1") (pintype "passive"))
      (node (ref "J13") (pin "2") (pinfunction "2_2") (pintype "passive"))
      (node (ref "LED1") (pin "1") (pinfunction "A_1") (pintype "passive"))
      (node (ref "MSP1") (pin "40") (pinfunction "VDD_40") (pintype "power_in"))
      (node (ref "R18") (pin "2") (pinfunction "2_2") (pintype "passive"))
      (node (ref "R2") (pin "2") (pinfunction "2_2") (pintype "passive"))
      (node (ref "R21") (pin "2") (pinfunction "2_2") (pintype "passive"))
      (node (ref "S1") (pin "4") (pinfunction "4_4") (pintype "passive"))
    )
    (net (code "79") (name "GND") (class "Default")
      (node (ref "C1") (pin "2") (pinfunction "2_2") (pintype "passive"))
      (node (ref "C10") (pin "1") (pinfunction "1_1") (pintype "passive"))
      (node (ref "C11") (pin "1") (pinfunction "1_1") (pintype "passive"))
      (node (ref "C12") (pin "1") (pinfunction "1_1") (pintype "passive"))
      (node (ref "C2") (pin "2") (pinfunction "2_2") (pintype "passive"))
      (node (ref "C3") (pin "2") (pinfunction "2_2") (pintype "passive"))
      (node (ref "C4") (pin "2") (pinfunction "2_2") (pintype "passive"))
      (node (ref "C6") (pin "2") (pinfunction "2_2") (pintype "passive"))
      (node (ref "C7") (pin "2") (pinfunction "2_2") (pintype "passive"))
      (node (ref "C9") (pin "1") (pinfunction "1_1") (pintype "passive"))
      (node (ref "D1") (pin "1") (pinfunction "ANODE_1") (pintype "passive"))
      (node (ref "J10") (pin "2") (pinfunction "2_2") (pintype "passive"))
      (node (ref "J10") (pin "3") (pinfunction "3_3") (pintype "passive"))
      (node (ref "J11") (pin "2") (pinfunction "2_2") (pintype "passive"))
      (node (ref "J11") (pin "3") (pinfunction "3_3") (pintype "passive"))
      (node (ref "J18") (pin "1") (pinfunction "1_1") (pintype "passive"))
      (node (ref "LED2") (pin "1") (pinfunction "K_1") (pintype "passive"))
      (node (ref "LED2") (pin "2") (pinfunction "K_2") (pintype "passive"))
      (node (ref "LED2") (pin "3") (pinfunction "K_3") (pintype "passive"))
      (node (ref "MSP1") (pin "41") (pinfunction "VSS_41") (pintype "power_in"))
      (node (ref "R14") (pin "1") (pinfunction "1_1") (pintype "passive"))
      (node (ref "R3") (pin "1") (pinfunction "1_1") (pintype "passive"))
      (node (ref "R8") (pin "2") (pinfunction "2_2") (pintype "passive"))
      (node (ref "S1") (pin "1") (pinfunction "1_1") (pintype "passive"))
      (node (ref "S1") (pin "2") (pinfunction "2_2") (pintype "passive"))
      (node (ref "S2") (pin "1") (pinfunction "1_1") (pintype "passive"))
      (node (ref "S2") (pin "2") (pinfunction "2_2") (pintype "passive"))
      (node (ref "S2") (pin "4") (pinfunction "4_4") (pintype "passive"))
      (node (ref "S3") (pin "1") (pinfunction "1_1") (pintype "passive"))
      (node (ref "S3") (pin "2") (pinfunction "2_2") (pintype "passive"))
      (node (ref "S3") (pin "3") (pinfunction "3_3") (pintype "passive"))
      (node (ref "Y2") (pin "2") (pinfunction "GND_2") (pintype "power_in"))
      (node (ref "Y2") (pin "4") (pinfunction "GND_4") (pintype "power_in"))
    )
    (net (code "80") (name "Net-(C5-Pad1)") (class "Default")
      (node (ref "C5") (pin "1") (pinfunction "1_1") (pintype "passive"))
      (node (ref "J16") (pin "1") (pinfunction "1_1") (pintype "passive"))
      (node (ref "R1") (pin "2") (pinfunction "2_2") (pintype "passive"))
    )
    (net (code "81") (name "Net-(D1-CATHODE)") (class "Default")
      (node (ref "C5") (pin "2") (pinfunction "2_2") (pintype "passive"))
      (node (ref "D1") (pin "2") (pinfunction "CATHODE_2") (pintype "passive"))
      (node (ref "J17") (pin "1") (pinfunction "1_1") (pintype "passive"))
      (node (ref "R1") (pin "1") (pinfunction "1_1") (pintype "passive"))
    )
    (net (code "82") (name "Net-(J4-Pad2)") (class "Default")
      (node (ref "J4") (pin "2") (pinfunction "2_2") (pintype "passive"))
      (node (ref "R4") (pin "1") (pinfunction "1_1") (pintype "passive"))
    )
    (net (code "83") (name "Net-(J5-Pad2)") (class "Default")
      (node (ref "J5") (pin "2") (pinfunction "2_2") (pintype "passive"))
      (node (ref "R5") (pin "1") (pinfunction "1_1") (pintype "passive"))
    )
    (net (code "84") (name "Net-(J6-Pad2)") (class "Default")
      (node (ref "J6") (pin "2") (pinfunction "2_2") (pintype "passive"))
      (node (ref "R6") (pin "1") (pinfunction "1_1") (pintype "passive"))
    )
    (net (code "85") (name "Net-(J7-Pad2)") (class "Default")
      (node (ref "J7") (pin "2") (pinfunction "2_2") (pintype "passive"))
      (node (ref "R7") (pin "1") (pinfunction "1_1") (pintype "passive"))
    )
    (net (code "86") (name "Net-(J8-Pad2)") (class "Default")
      (node (ref "J8") (pin "2") (pinfunction "2_2") (pintype "passive"))
      (node (ref "R14") (pin "2") (pinfunction "2_2") (pintype "passive"))
      (node (ref "S1") (pin "3") (pinfunction "3_3") (pintype "passive"))
    )
    (net (code "87") (name "Net-(J19-Pad1)") (class "Default")
      (node (ref "J19") (pin "1") (pinfunction "1_1") (pintype "passive"))
      (node (ref "R18") (pin "1") (pinfunction "1_1") (pintype "passive"))
    )
    (net (code "88") (name "Net-(J19-Pad3)") (class "Default")
      (node (ref "J19") (pin "3") (pinfunction "3_3") (pintype "passive"))
      (node (ref "R12") (pin "1") (pinfunction "1_1") (pintype "passive"))
    )
    (net (code "89") (name "Net-(J20-Pad1)") (class "Default")
      (node (ref "J20") (pin "1") (pinfunction "1_1") (pintype "passive"))
      (node (ref "R21") (pin "1") (pinfunction "1_1") (pintype "passive"))
    )
    (net (code "90") (name "Net-(J20-Pad3)") (class "Default")
      (node (ref "J20") (pin "3") (pinfunction "3_3") (pintype "passive"))
      (node (ref "R16") (pin "1") (pinfunction "1_1") (pintype "passive"))
    )
    (net (code "91") (name "Net-(LED1-K)") (class "Default")
      (node (ref "LED1") (pin "2") (pinfunction "K_2") (pintype "passive"))
      (node (ref "R4") (pin "2") (pinfunction "2_2") (pintype "passive"))
    )
    (net (code "92") (name "Net-(LED2-A-Pad4)") (class "Default")
      (node (ref "LED2") (pin "4") (pinfunction "A_4") (pintype "passive"))
      (node (ref "R5") (pin "2") (pinfunction "2_2") (pintype "passive"))
    )
    (net (code "93") (name "Net-(LED2-A-Pad5)") (class "Default")
      (node (ref "LED2") (pin "5") (pinfunction "A_5") (pintype "passive"))
      (node (ref "R6") (pin "2") (pinfunction "2_2") (pintype "passive"))
    )
    (net (code "94") (name "Net-(LED2-A-Pad6)") (class "Default")
      (node (ref "LED2") (pin "6") (pinfunction "A_6") (pintype "passive"))
      (node (ref "R7") (pin "2") (pinfunction "2_2") (pintype "passive"))
    )
    (net (code "95") (name "Net-(MSP1-VCORE)") (class "Default")
      (node (ref "C3") (pin "1") (pinfunction "1_1") (pintype "passive"))
      (node (ref "C4") (pin "1") (pinfunction "1_1") (pintype "passive"))
      (node (ref "MSP1") (pin "32") (pinfunction "VCORE_32") (pintype "power_in"))
    )
  )
)
